# bluetooth.net
KiCad netlist of a schematic drawn in Altium Designer
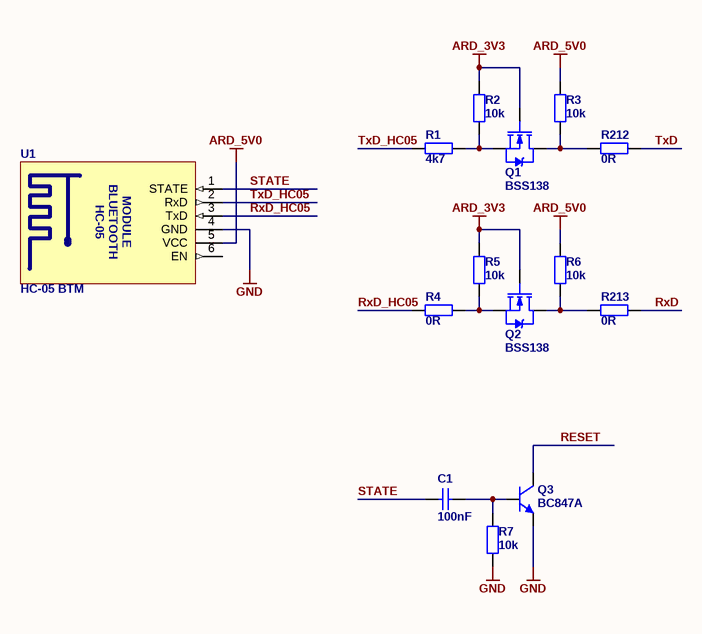
[diagram p0: bluetooth.SchDoc]

(export (version "E")
  (design (tool "Eeschema 10.0.6"))
  (components
    (comp (ref "C1")
      (value "100nF")
      (footprint "C0805")
      (description "Capacitor")
      (libsource (lib "capacitors") (part "Cap"))
    )
    (comp (ref "Q1")
      (value "BSS138")
      (footprint "SOT-23")
      (description "N-Channel Enhancement Mode Vertical DMOS FET")
      (fields (field (name "PUBLISHER") "Altium Limited"))
      (libsource (lib "transistors_mos") (part "BSS138"))
    )
    (comp (ref "Q2")
      (value "BSS138")
      (footprint "SOT-23")
      (description "N-Channel Enhancement Mode Vertical DMOS FET")
      (fields (field (name "PUBLISHER") "Altium Limited"))
      (libsource (lib "transistors_mos") (part "BSS138"))
    )
    (comp (ref "Q3")
      (value "BC847A")
      (footprint "SOT-23")
      (description "NPN General Purpose Transistor (VCE=45V, IC=100mA, HFE=110-220)")
      (libsource (lib "transistors_bjt") (part "BC847A"))
    )
    (comp (ref "R1")
      (value "4k7")
      (footprint "R0805")
      (description "Resistor")
      (libsource (lib "") (part "Res_1"))
    )
    (comp (ref "R2")
      (value "10k")
      (footprint "R0805")
      (description "Resistor")
      (libsource (lib "resistors") (part "Res"))
    )
    (comp (ref "R3")
      (value "10k")
      (footprint "R0805")
      (description "Resistor")
      (libsource (lib "resistors") (part "Res"))
    )
    (comp (ref "R4")
      (value "0R")
      (footprint "R0805")
      (description "Resistor")
      (libsource (lib "") (part "Res_1"))
    )
    (comp (ref "R5")
      (value "10k")
      (footprint "R0805")
      (description "Resistor")
      (libsource (lib "resistors") (part "Res"))
    )
    (comp (ref "R6")
      (value "10k")
      (footprint "R0805")
      (description "Resistor")
      (libsource (lib "resistors") (part "Res"))
    )
    (comp (ref "R7")
      (value "10k")
      (footprint "R0805")
      (description "Resistor")
      (libsource (lib "resistors") (part "Res"))
    )
    (comp (ref "R212")
      (value "0R")
      (footprint "R0805")
      (description "Resistor")
      (libsource (lib "") (part "Res_1"))
    )
    (comp (ref "R213")
      (value "0R")
      (footprint "R0805")
      (description "Resistor")
      (libsource (lib "") (part "Res_1"))
    )
    (comp (ref "U1")
      (value "HC-05 BTM")
      (footprint "HC-05_H")
      (description "HC-05 Bluetooth Module")
      (libsource (lib "wireless_modules") (part "HC-05_BTM"))
    )
  )
  (nets
    (net (code "1") (name "/RESET") (class "Default")
      (node (ref "Q3") (pin "3") (pinfunction "C_3") (pintype "passive"))
    )
    (net (code "2") (name "/RxD") (class "Default")
      (node (ref "R213") (pin "2") (pinfunction "2_2") (pintype "passive"))
    )
    (net (code "3") (name "/RxD_HC05") (class "Default")
      (node (ref "R4") (pin "1") (pinfunction "1_1") (pintype "passive"))
      (node (ref "U1") (pin "3") (pinfunction "TxD_3") (pintype "input"))
    )
    (net (code "4") (name "/STATE") (class "Default")
      (node (ref "C1") (pin "1") (pinfunction "1_1") (pintype "passive"))
      (node (ref "U1") (pin "1") (pinfunction "STATE_1") (pintype "input"))
    )
    (net (code "5") (name "/TxD") (class "Default")
      (node (ref "R212") (pin "2") (pinfunction "2_2") (pintype "passive"))
    )
    (net (code "6") (name "/TxD_HC05") (class "Default")
      (node (ref "R1") (pin "1") (pinfunction "1_1") (pintype "passive"))
      (node (ref "U1") (pin "2") (pinfunction "RxD_2") (pintype "output"))
    )
    (net (code "7") (name "ARD_3V3") (class "Default")
      (node (ref "Q1") (pin "1") (pinfunction "G_1") (pintype "passive"))
      (node (ref "Q2") (pin "1") (pinfunction "G_1") (pintype "passive"))
      (node (ref "R2") (pin "1") (pinfunction "1_1") (pintype "passive"))
      (node (ref "R5") (pin "1") (pinfunction "1_1") (pintype "passive"))
    )
    (net (code "8") (name "ARD_5V0") (class "Default")
      (node (ref "R3") (pin "1") (pinfunction "1_1") (pintype "passive"))
      (node (ref "R6") (pin "1") (pinfunction "1_1") (pintype "passive"))
      (node (ref "U1") (pin "5") (pinfunction "VCC_5") (pintype "power_in"))
    )
    (net (code "9") (name "GND") (class "Default")
      (node (ref "Q3") (pin "2") (pinfunction "E_2") (pintype "passive"))
      (node (ref "R7") (pin "2") (pinfunction "2_2") (pintype "passive"))
      (node (ref "U1") (pin "4") (pinfunction "GND_4") (pintype "power_in"))
    )
    (net (code "10") (name "Net-(Q1-D)") (class "Default")
      (node (ref "Q1") (pin "3") (pinfunction "D_3") (pintype "passive"))
      (node (ref "R212") (pin "1") (pinfunction "1_1") (pintype "passive"))
      (node (ref "R3") (pin "2") (pinfunction "2_2") (pintype "passive"))
    )
    (net (code "11") (name "Net-(Q1-S)") (class "Default")
      (node (ref "Q1") (pin "2") (pinfunction "S_2") (pintype "passive"))
      (node (ref "R1") (pin "2") (pinfunction "2_2") (pintype "passive"))
      (node (ref "R2") (pin "2") (pinfunction "2_2") (pintype "passive"))
    )
    (net (code "12") (name "Net-(Q2-D)") (class "Default")
      (node (ref "Q2") (pin "3") (pinfunction "D_3") (pintype "passive"))
      (node (ref "R213") (pin "1") (pinfunction "1_1") (pintype "passive"))
      (node (ref "R6") (pin "2") (pinfunction "2_2") (pintype "passive"))
    )
    (net (code "13") (name "Net-(Q2-S)") (class "Default")
      (node (ref "Q2") (pin "2") (pinfunction "S_2") (pintype "passive"))
      (node (ref "R4") (pin "2") (pinfunction "2_2") (pintype "passive"))
      (node (ref "R5") (pin "2") (pinfunction "2_2") (pintype "passive"))
    )
    (net (code "14") (name "Net-(Q3-B)") (class "Default")
      (node (ref "C1") (pin "2") (pinfunction "2_2") (pintype "passive"))
      (node (ref "Q3") (pin "1") (pinfunction "B_1") (pintype "passive"))
      (node (ref "R7") (pin "1") (pinfunction "1_1") (pintype "passive"))
    )
    (net (code "15") (name "unconnected-(U1-EN-Pad6)") (class "Default")
      (node (ref "U1") (pin "6") (pinfunction "EN_6") (pintype "output"))
    )
  )
)
